# PiLoraGatewayV2_4.net
KiCad netlist of a schematic drawn in EAGLE
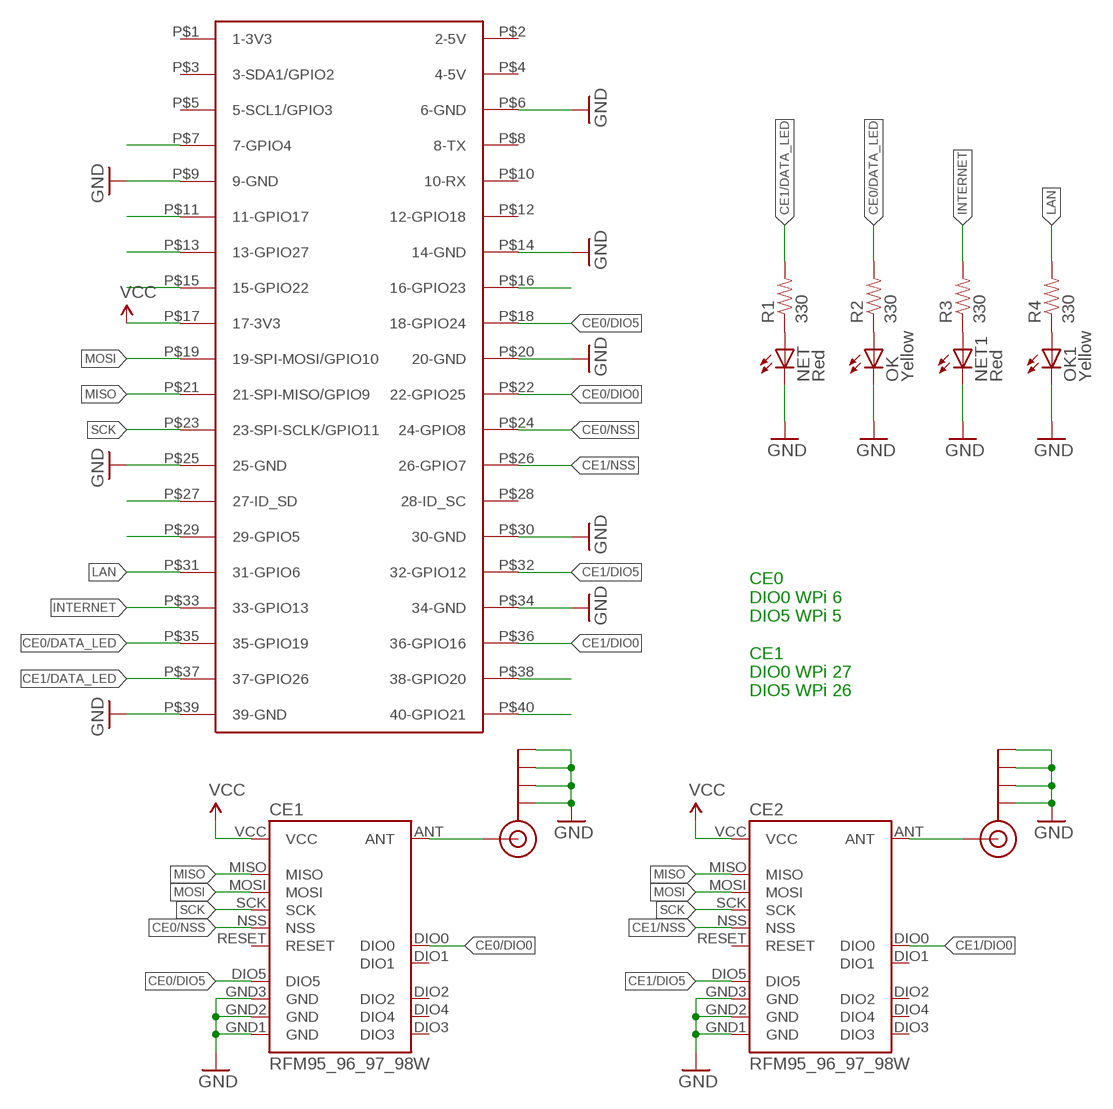
[diagram p0: schematic, sheet 1]

(export (version "E")
  (design (tool "Eeschema 10.0.6"))
  (components
    (comp (ref "CE1")
      (value "RFM95_96_97_98W")
      (footprint "eagle-import:RFM95_96_97_98W")
      (libsource (lib "eagle-import") (part "RFM95_96_97_98W"))
    )
    (comp (ref "CE2")
      (value "RFM95_96_97_98W")
      (footprint "eagle-import:RFM95_96_97_98W")
      (libsource (lib "eagle-import") (part "RFM95_96_97_98W"))
    )
    (comp (ref "J$1")
      (value "SMA_EDGE")
      (footprint "eagle-import:SMA-EDGE")
      (libsource (lib "eagle-import") (part "SMA_EDGE"))
    )
    (comp (ref "J$2")
      (value "SMA_EDGE")
      (footprint "eagle-import:SMA-EDGE")
      (libsource (lib "eagle-import") (part "SMA_EDGE"))
    )
    (comp (ref "NET")
      (value "Red")
      (footprint "eagle-import:LED-0603")
      (libsource (lib "eagle-import") (part "LED0603"))
    )
    (comp (ref "NET1")
      (value "Red")
      (footprint "eagle-import:LED-0603")
      (libsource (lib "eagle-import") (part "LED0603"))
    )
    (comp (ref "OK")
      (value "Yellow")
      (footprint "eagle-import:LED-0603")
      (libsource (lib "eagle-import") (part "LED0603"))
    )
    (comp (ref "OK1")
      (value "Yellow")
      (footprint "eagle-import:LED-0603")
      (libsource (lib "eagle-import") (part "LED0603"))
    )
    (comp (ref "R1")
      (value "330")
      (footprint "eagle-import:0603-RES")
      (libsource (lib "eagle-import") (part "RESISTOR0603-RES"))
    )
    (comp (ref "R2")
      (value "330")
      (footprint "eagle-import:0603-RES")
      (libsource (lib "eagle-import") (part "RESISTOR0603-RES"))
    )
    (comp (ref "R3")
      (value "330")
      (footprint "eagle-import:0603-RES")
      (libsource (lib "eagle-import") (part "RESISTOR0603-RES"))
    )
    (comp (ref "R4")
      (value "330")
      (footprint "eagle-import:0603-RES")
      (libsource (lib "eagle-import") (part "RESISTOR0603-RES"))
    )
    (comp (ref "U$1")
      (value "RASPBERRY-PI+")
      (footprint "eagle-import:RASPBERRY-PI-PLUS-CAM_NOTCH")
      (libsource (lib "eagle-import") (part "RASPBERRY-PI+"))
    )
  )
  (nets
    (net (code "1") (name "CE0{slash}DATA_LED") (class "Default")
      (node (ref "R2") (pin "2") (pinfunction "2_2") (pintype "passive"))
      (node (ref "U$1") (pin "P$35") (pinfunction "35-GPIO19_P$35") (pintype "bidirectional"))
    )
    (net (code "2") (name "CE0{slash}DIO0") (class "Default")
      (node (ref "CE1") (pin "DIO0") (pinfunction "DIO0_DIO0") (pintype "input"))
      (node (ref "U$1") (pin "P$22") (pinfunction "22-GPIO25_P$22") (pintype "bidirectional"))
    )
    (net (code "3") (name "CE0{slash}DIO5") (class "Default")
      (node (ref "CE1") (pin "DIO5") (pinfunction "DIO5_DIO5") (pintype "input"))
      (node (ref "U$1") (pin "P$18") (pinfunction "18-GPIO24_P$18") (pintype "bidirectional"))
    )
    (net (code "4") (name "CE0{slash}NSS") (class "Default")
      (node (ref "CE1") (pin "NSS") (pinfunction "NSS_NSS") (pintype "input"))
      (node (ref "U$1") (pin "P$24") (pinfunction "24-GPIO8_P$24") (pintype "bidirectional"))
    )
    (net (code "5") (name "CE1{slash}DATA_LED") (class "Default")
      (node (ref "R1") (pin "2") (pinfunction "2_2") (pintype "passive"))
      (node (ref "U$1") (pin "P$37") (pinfunction "37-GPIO26_P$37") (pintype "bidirectional"))
    )
    (net (code "6") (name "CE1{slash}DIO0") (class "Default")
      (node (ref "CE2") (pin "DIO0") (pinfunction "DIO0_DIO0") (pintype "input"))
      (node (ref "U$1") (pin "P$36") (pinfunction "36-GPIO16_P$36") (pintype "bidirectional"))
    )
    (net (code "7") (name "CE1{slash}DIO5") (class "Default")
      (node (ref "CE2") (pin "DIO5") (pinfunction "DIO5_DIO5") (pintype "input"))
      (node (ref "U$1") (pin "P$32") (pinfunction "32-GPIO12_P$32") (pintype "bidirectional"))
    )
    (net (code "8") (name "CE1{slash}NSS") (class "Default")
      (node (ref "CE2") (pin "NSS") (pinfunction "NSS_NSS") (pintype "input"))
      (node (ref "U$1") (pin "P$26") (pinfunction "26-GPIO7_P$26") (pintype "bidirectional"))
    )
    (net (code "9") (name "GND") (class "Default")
      (node (ref "CE1") (pin "GND1") (pinfunction "GND_GND1") (pintype "power_in"))
      (node (ref "CE1") (pin "GND2") (pinfunction "GND_GND2") (pintype "power_in"))
      (node (ref "CE1") (pin "GND3") (pinfunction "GND_GND3") (pintype "power_in"))
      (node (ref "CE2") (pin "GND1") (pinfunction "GND_GND1") (pintype "power_in"))
      (node (ref "CE2") (pin "GND2") (pinfunction "GND_GND2") (pintype "power_in"))
      (node (ref "CE2") (pin "GND3") (pinfunction "GND_GND3") (pintype "power_in"))
      (node (ref "J$1") (pin "GND@0") (pinfunction "GND_GND@0") (pintype "bidirectional"))
      (node (ref "J$1") (pin "GND@1") (pinfunction "GND_GND@1") (pintype "bidirectional"))
      (node (ref "J$1") (pin "GND@2") (pinfunction "GND_GND@2") (pintype "bidirectional"))
      (node (ref "J$1") (pin "GND@3") (pinfunction "GND_GND@3") (pintype "bidirectional"))
      (node (ref "J$2") (pin "GND@0") (pinfunction "GND_GND@0") (pintype "bidirectional"))
      (node (ref "J$2") (pin "GND@1") (pinfunction "GND_GND@1") (pintype "bidirectional"))
      (node (ref "J$2") (pin "GND@2") (pinfunction "GND_GND@2") (pintype "bidirectional"))
      (node (ref "J$2") (pin "GND@3") (pinfunction "GND_GND@3") (pintype "bidirectional"))
      (node (ref "NET") (pin "C") (pinfunction "C_C") (pintype "passive"))
      (node (ref "NET1") (pin "C") (pinfunction "C_C") (pintype "passive"))
      (node (ref "OK") (pin "C") (pinfunction "C_C") (pintype "passive"))
      (node (ref "OK1") (pin "C") (pinfunction "C_C") (pintype "passive"))
      (node (ref "U$1") (pin "P$14") (pinfunction "14-GND_P$14") (pintype "bidirectional"))
      (node (ref "U$1") (pin "P$20") (pinfunction "20-GND_P$20") (pintype "bidirectional"))
      (node (ref "U$1") (pin "P$25") (pinfunction "25-GND_P$25") (pintype "bidirectional"))
      (node (ref "U$1") (pin "P$30") (pinfunction "30-GND_P$30") (pintype "bidirectional"))
      (node (ref "U$1") (pin "P$34") (pinfunction "34-GND_P$34") (pintype "bidirectional"))
      (node (ref "U$1") (pin "P$39") (pinfunction "39-GND_P$39") (pintype "bidirectional"))
      (node (ref "U$1") (pin "P$6") (pinfunction "6-GND_P$6") (pintype "bidirectional"))
      (node (ref "U$1") (pin "P$9") (pinfunction "9-GND_P$9") (pintype "bidirectional"))
    )
    (net (code "10") (name "INTERNET") (class "Default")
      (node (ref "R3") (pin "2") (pinfunction "2_2") (pintype "passive"))
      (node (ref "U$1") (pin "P$33") (pinfunction "33-GPIO13_P$33") (pintype "bidirectional"))
    )
    (net (code "11") (name "LAN") (class "Default")
      (node (ref "R4") (pin "2") (pinfunction "2_2") (pintype "passive"))
      (node (ref "U$1") (pin "P$31") (pinfunction "31-GPIO6_P$31") (pintype "bidirectional"))
    )
    (net (code "12") (name "MISO") (class "Default")
      (node (ref "CE1") (pin "MISO") (pinfunction "MISO_MISO") (pintype "output"))
      (node (ref "CE2") (pin "MISO") (pinfunction "MISO_MISO") (pintype "output"))
      (node (ref "U$1") (pin "P$21") (pinfunction "21-SPI-MISO/GPIO9_P$21") (pintype "bidirectional"))
    )
    (net (code "13") (name "MOSI") (class "Default")
      (node (ref "CE1") (pin "MOSI") (pinfunction "MOSI_MOSI") (pintype "input"))
      (node (ref "CE2") (pin "MOSI") (pinfunction "MOSI_MOSI") (pintype "input"))
      (node (ref "U$1") (pin "P$19") (pinfunction "19-SPI-MOSI/GPIO10_P$19") (pintype "bidirectional"))
    )
    (net (code "14") (name "Net-(J$1-SIGNAL)") (class "Default")
      (node (ref "CE1") (pin "ANT") (pinfunction "ANT_ANT") (pintype "bidirectional"))
      (node (ref "J$1") (pin "SIG") (pinfunction "SIGNAL_SIG") (pintype "bidirectional"))
    )
    (net (code "15") (name "Net-(J$2-SIGNAL)") (class "Default")
      (node (ref "CE2") (pin "ANT") (pinfunction "ANT_ANT") (pintype "bidirectional"))
      (node (ref "J$2") (pin "SIG") (pinfunction "SIGNAL_SIG") (pintype "bidirectional"))
    )
    (net (code "16") (name "Net-(NET-PadA)") (class "Default")
      (node (ref "NET") (pin "A") (pinfunction "A_A") (pintype "passive"))
      (node (ref "R1") (pin "1") (pinfunction "1_1") (pintype "passive"))
    )
    (net (code "17") (name "Net-(NET1-PadA)") (class "Default")
      (node (ref "NET1") (pin "A") (pinfunction "A_A") (pintype "passive"))
      (node (ref "R3") (pin "1") (pinfunction "1_1") (pintype "passive"))
    )
    (net (code "18") (name "Net-(OK-PadA)") (class "Default")
      (node (ref "OK") (pin "A") (pinfunction "A_A") (pintype "passive"))
      (node (ref "R2") (pin "1") (pinfunction "1_1") (pintype "passive"))
    )
    (net (code "19") (name "Net-(OK1-PadA)") (class "Default")
      (node (ref "OK1") (pin "A") (pinfunction "A_A") (pintype "passive"))
      (node (ref "R4") (pin "1") (pinfunction "1_1") (pintype "passive"))
    )
    (net (code "20") (name "SCK") (class "Default")
      (node (ref "CE1") (pin "SCK") (pinfunction "SCK_SCK") (pintype "input"))
      (node (ref "CE2") (pin "SCK") (pinfunction "SCK_SCK") (pintype "input"))
      (node (ref "U$1") (pin "P$23") (pinfunction "23-SPI-SCLK/GPIO11_P$23") (pintype "bidirectional"))
    )
    (net (code "21") (name "VCC") (class "Default")
      (node (ref "CE1") (pin "VCC") (pinfunction "VCC_VCC") (pintype "bidirectional"))
      (node (ref "CE2") (pin "VCC") (pinfunction "VCC_VCC") (pintype "bidirectional"))
      (node (ref "U$1") (pin "P$17") (pinfunction "17-3V3_P$17") (pintype "bidirectional"))
    )
    (net (code "22") (name "unconnected-(CE1-PadDIO1)") (class "Default")
      (node (ref "CE1") (pin "DIO1") (pinfunction "DIO1_DIO1") (pintype "input"))
    )
    (net (code "23") (name "unconnected-(CE1-PadDIO2)") (class "Default")
      (node (ref "CE1") (pin "DIO2") (pinfunction "DIO2_DIO2") (pintype "bidirectional"))
    )
    (net (code "24") (name "unconnected-(CE1-PadDIO3)") (class "Default")
      (node (ref "CE1") (pin "DIO3") (pinfunction "DIO3_DIO3") (pintype "bidirectional"))
    )
    (net (code "25") (name "unconnected-(CE1-PadDIO4)") (class "Default")
      (node (ref "CE1") (pin "DIO4") (pinfunction "DIO4_DIO4") (pintype "bidirectional"))
    )
    (net (code "26") (name "unconnected-(CE1-PadRESET)") (class "Default")
      (node (ref "CE1") (pin "RESET") (pinfunction "RESET_RESET") (pintype "output"))
    )
    (net (code "27") (name "unconnected-(CE2-PadDIO1)") (class "Default")
      (node (ref "CE2") (pin "DIO1") (pinfunction "DIO1_DIO1") (pintype "input"))
    )
    (net (code "28") (name "unconnected-(CE2-PadDIO2)") (class "Default")
      (node (ref "CE2") (pin "DIO2") (pinfunction "DIO2_DIO2") (pintype "bidirectional"))
    )
    (net (code "29") (name "unconnected-(CE2-PadDIO3)") (class "Default")
      (node (ref "CE2") (pin "DIO3") (pinfunction "DIO3_DIO3") (pintype "bidirectional"))
    )
    (net (code "30") (name "unconnected-(CE2-PadDIO4)") (class "Default")
      (node (ref "CE2") (pin "DIO4") (pinfunction "DIO4_DIO4") (pintype "bidirectional"))
    )
    (net (code "31") (name "unconnected-(CE2-PadRESET)") (class "Default")
      (node (ref "CE2") (pin "RESET") (pinfunction "RESET_RESET") (pintype "output"))
    )
    (net (code "32") (name "unconnected-(U$1-1-3V3-PadP$1)") (class "Default")
      (node (ref "U$1") (pin "P$1") (pinfunction "1-3V3_P$1") (pintype "bidirectional"))
    )
    (net (code "33") (name "unconnected-(U$1-2-5V-PadP$2)") (class "Default")
      (node (ref "U$1") (pin "P$2") (pinfunction "2-5V_P$2") (pintype "bidirectional"))
    )
    (net (code "34") (name "unconnected-(U$1-3-SDA1{slash}GPIO2-PadP$3)") (class "Default")
      (node (ref "U$1") (pin "P$3") (pinfunction "3-SDA1/GPIO2_P$3") (pintype "bidirectional"))
    )
    (net (code "35") (name "unconnected-(U$1-4-5V-PadP$4)") (class "Default")
      (node (ref "U$1") (pin "P$4") (pinfunction "4-5V_P$4") (pintype "bidirectional"))
    )
    (net (code "36") (name "unconnected-(U$1-5-SCL1{slash}GPIO3-PadP$5)") (class "Default")
      (node (ref "U$1") (pin "P$5") (pinfunction "5-SCL1/GPIO3_P$5") (pintype "bidirectional"))
    )
    (net (code "37") (name "unconnected-(U$1-7-GPIO4-PadP$7)") (class "Default")
      (node (ref "U$1") (pin "P$7") (pinfunction "7-GPIO4_P$7") (pintype "bidirectional"))
    )
    (net (code "38") (name "unconnected-(U$1-8-TX-PadP$8)") (class "Default")
      (node (ref "U$1") (pin "P$8") (pinfunction "8-TX_P$8") (pintype "bidirectional"))
    )
    (net (code "39") (name "unconnected-(U$1-10-RX-PadP$10)") (class "Default")
      (node (ref "U$1") (pin "P$10") (pinfunction "10-RX_P$10") (pintype "bidirectional"))
    )
    (net (code "40") (name "unconnected-(U$1-11-GPIO17-PadP$11)") (class "Default")
      (node (ref "U$1") (pin "P$11") (pinfunction "11-GPIO17_P$11") (pintype "bidirectional"))
    )
    (net (code "41") (name "unconnected-(U$1-12-GPIO18-PadP$12)") (class "Default")
      (node (ref "U$1") (pin "P$12") (pinfunction "12-GPIO18_P$12") (pintype "bidirectional"))
    )
    (net (code "42") (name "unconnected-(U$1-13-GPIO27-PadP$13)") (class "Default")
      (node (ref "U$1") (pin "P$13") (pinfunction "13-GPIO27_P$13") (pintype "bidirectional"))
    )
    (net (code "43") (name "unconnected-(U$1-15-GPIO22-PadP$15)") (class "Default")
      (node (ref "U$1") (pin "P$15") (pinfunction "15-GPIO22_P$15") (pintype "bidirectional"))
    )
    (net (code "44") (name "unconnected-(U$1-16-GPIO23-PadP$16)") (class "Default")
      (node (ref "U$1") (pin "P$16") (pinfunction "16-GPIO23_P$16") (pintype "bidirectional"))
    )
    (net (code "45") (name "unconnected-(U$1-27-ID_SD-PadP$27)") (class "Default")
      (node (ref "U$1") (pin "P$27") (pinfunction "27-ID_SD_P$27") (pintype "bidirectional"))
    )
    (net (code "46") (name "unconnected-(U$1-28-ID_SC-PadP$28)") (class "Default")
      (node (ref "U$1") (pin "P$28") (pinfunction "28-ID_SC_P$28") (pintype "bidirectional"))
    )
    (net (code "47") (name "unconnected-(U$1-29-GPIO5-PadP$29)") (class "Default")
      (node (ref "U$1") (pin "P$29") (pinfunction "29-GPIO5_P$29") (pintype "bidirectional"))
    )
    (net (code "48") (name "unconnected-(U$1-38-GPIO20-PadP$38)") (class "Default")
      (node (ref "U$1") (pin "P$38") (pinfunction "38-GPIO20_P$38") (pintype "bidirectional"))
    )
    (net (code "49") (name "unconnected-(U$1-40-GPIO21-PadP$40)") (class "Default")
      (node (ref "U$1") (pin "P$40") (pinfunction "40-GPIO21_P$40") (pintype "bidirectional"))
    )
  )
)
